# Current_Sensor_v0_6.net
KiCad netlist of a schematic drawn in EAGLE
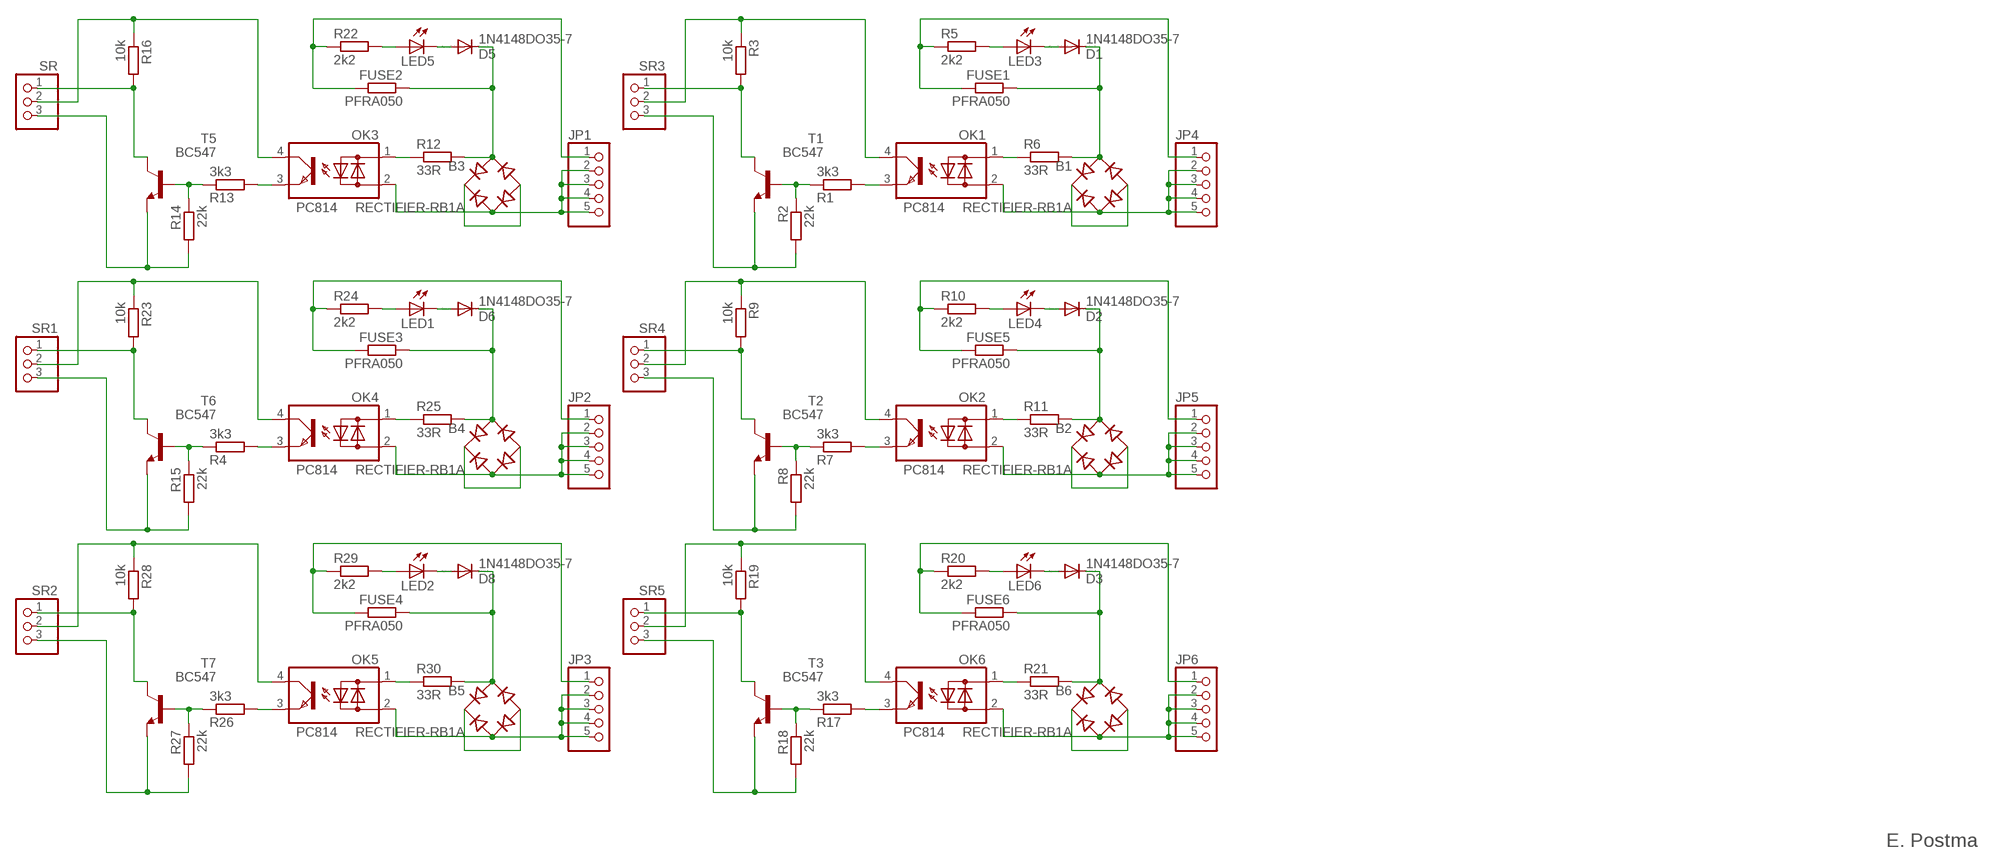
[diagram p0: schematic, sheet 1]

(export (version "E")
  (design (tool "Eeschema 10.0.6"))
  (components
    (comp (ref "B1")
      (value "RECTIFIER-RB1A")
      (footprint "eagle-import:RB1A")
      (libsource (lib "eagle-import") (part "RECTIFIER-RB1A"))
    )
    (comp (ref "B2")
      (value "RECTIFIER-RB1A")
      (footprint "eagle-import:RB1A")
      (libsource (lib "eagle-import") (part "RECTIFIER-RB1A"))
    )
    (comp (ref "B3")
      (value "RECTIFIER-RB1A")
      (footprint "eagle-import:RB1A")
      (libsource (lib "eagle-import") (part "RECTIFIER-RB1A"))
    )
    (comp (ref "B4")
      (value "RECTIFIER-RB1A")
      (footprint "eagle-import:RB1A")
      (libsource (lib "eagle-import") (part "RECTIFIER-RB1A"))
    )
    (comp (ref "B5")
      (value "RECTIFIER-RB1A")
      (footprint "eagle-import:RB1A")
      (libsource (lib "eagle-import") (part "RECTIFIER-RB1A"))
    )
    (comp (ref "B6")
      (value "RECTIFIER-RB1A")
      (footprint "eagle-import:RB1A")
      (libsource (lib "eagle-import") (part "RECTIFIER-RB1A"))
    )
    (comp (ref "D1")
      (value "1N4148DO35-7")
      (footprint "eagle-import:DO35-7")
      (libsource (lib "eagle-import") (part "1N4148DO35-7"))
    )
    (comp (ref "D2")
      (value "1N4148DO35-7")
      (footprint "eagle-import:DO35-7")
      (libsource (lib "eagle-import") (part "1N4148DO35-7"))
    )
    (comp (ref "D3")
      (value "1N4148DO35-7")
      (footprint "eagle-import:DO35-7")
      (libsource (lib "eagle-import") (part "1N4148DO35-7"))
    )
    (comp (ref "D5")
      (value "1N4148DO35-7")
      (footprint "eagle-import:DO35-7")
      (libsource (lib "eagle-import") (part "1N4148DO35-7"))
    )
    (comp (ref "D6")
      (value "1N4148DO35-7")
      (footprint "eagle-import:DO35-7")
      (libsource (lib "eagle-import") (part "1N4148DO35-7"))
    )
    (comp (ref "D8")
      (value "1N4148DO35-7")
      (footprint "eagle-import:DO35-7")
      (libsource (lib "eagle-import") (part "1N4148DO35-7"))
    )
    (comp (ref "FUSE1")
      (value "PFRA050")
      (footprint "eagle-import:0414V")
      (libsource (lib "eagle-import") (part "R-EU_0414/5V"))
    )
    (comp (ref "FUSE2")
      (value "PFRA050")
      (footprint "eagle-import:0414V")
      (libsource (lib "eagle-import") (part "R-EU_0414/5V"))
    )
    (comp (ref "FUSE3")
      (value "PFRA050")
      (footprint "eagle-import:0414V")
      (libsource (lib "eagle-import") (part "R-EU_0414/5V"))
    )
    (comp (ref "FUSE4")
      (value "PFRA050")
      (footprint "eagle-import:0414V")
      (libsource (lib "eagle-import") (part "R-EU_0414/5V"))
    )
    (comp (ref "FUSE5")
      (value "PFRA050")
      (footprint "eagle-import:0414V")
      (libsource (lib "eagle-import") (part "R-EU_0414/5V"))
    )
    (comp (ref "FUSE6")
      (value "PFRA050")
      (footprint "eagle-import:0414V")
      (libsource (lib "eagle-import") (part "R-EU_0414/5V"))
    )
    (comp (ref "JP1")
      (value "PINHD-1X5")
      (footprint "eagle-import:1X05")
      (libsource (lib "eagle-import") (part "PINHD-1X5"))
    )
    (comp (ref "JP2")
      (value "PINHD-1X5")
      (footprint "eagle-import:1X05")
      (libsource (lib "eagle-import") (part "PINHD-1X5"))
    )
    (comp (ref "JP3")
      (value "PINHD-1X5")
      (footprint "eagle-import:1X05")
      (libsource (lib "eagle-import") (part "PINHD-1X5"))
    )
    (comp (ref "JP4")
      (value "PINHD-1X5")
      (footprint "eagle-import:1X05")
      (libsource (lib "eagle-import") (part "PINHD-1X5"))
    )
    (comp (ref "JP5")
      (value "PINHD-1X5")
      (footprint "eagle-import:1X05")
      (libsource (lib "eagle-import") (part "PINHD-1X5"))
    )
    (comp (ref "JP6")
      (value "PINHD-1X5")
      (footprint "eagle-import:1X05")
      (libsource (lib "eagle-import") (part "PINHD-1X5"))
    )
    (comp (ref "LED1")
      (value "LED3MM")
      (footprint "eagle-import:LED3MM")
      (libsource (lib "eagle-import") (part "LED3MM"))
    )
    (comp (ref "LED2")
      (value "LED3MM")
      (footprint "eagle-import:LED3MM")
      (libsource (lib "eagle-import") (part "LED3MM"))
    )
    (comp (ref "LED3")
      (value "LED3MM")
      (footprint "eagle-import:LED3MM")
      (libsource (lib "eagle-import") (part "LED3MM"))
    )
    (comp (ref "LED4")
      (value "LED3MM")
      (footprint "eagle-import:LED3MM")
      (libsource (lib "eagle-import") (part "LED3MM"))
    )
    (comp (ref "LED5")
      (value "LED3MM")
      (footprint "eagle-import:LED3MM")
      (libsource (lib "eagle-import") (part "LED3MM"))
    )
    (comp (ref "LED6")
      (value "LED3MM")
      (footprint "eagle-import:LED3MM")
      (libsource (lib "eagle-import") (part "LED3MM"))
    )
    (comp (ref "OK1")
      (value "PC814")
      (footprint "eagle-import:DIL04")
      (libsource (lib "eagle-import") (part "PC814"))
    )
    (comp (ref "OK2")
      (value "PC814")
      (footprint "eagle-import:DIL04")
      (libsource (lib "eagle-import") (part "PC814"))
    )
    (comp (ref "OK3")
      (value "PC814")
      (footprint "eagle-import:DIL04")
      (libsource (lib "eagle-import") (part "PC814"))
    )
    (comp (ref "OK4")
      (value "PC814")
      (footprint "eagle-import:DIL04")
      (libsource (lib "eagle-import") (part "PC814"))
    )
    (comp (ref "OK5")
      (value "PC814")
      (footprint "eagle-import:DIL04")
      (libsource (lib "eagle-import") (part "PC814"))
    )
    (comp (ref "OK6")
      (value "PC814")
      (footprint "eagle-import:DIL04")
      (libsource (lib "eagle-import") (part "PC814"))
    )
    (comp (ref "R1")
      (value "3k3")
      (footprint "eagle-import:0207_7")
      (libsource (lib "eagle-import") (part "resistor_348_R-EU_0207/7"))
    )
    (comp (ref "R2")
      (value "22k")
      (footprint "eagle-import:0207_7")
      (libsource (lib "eagle-import") (part "resistor_348_R-EU_0207/7"))
    )
    (comp (ref "R3")
      (value "10k")
      (footprint "eagle-import:0207_7")
      (libsource (lib "eagle-import") (part "resistor_348_R-EU_0207/7"))
    )
    (comp (ref "R4")
      (value "3k3")
      (footprint "eagle-import:0207_7")
      (libsource (lib "eagle-import") (part "resistor_348_R-EU_0207/7"))
    )
    (comp (ref "R5")
      (value "2k2")
      (footprint "eagle-import:0207_7")
      (libsource (lib "eagle-import") (part "resistor_348_R-EU_0207/7"))
    )
    (comp (ref "R6")
      (value "33R")
      (footprint "eagle-import:0207_7")
      (libsource (lib "eagle-import") (part "resistor_348_R-EU_0207/7"))
    )
    (comp (ref "R7")
      (value "3k3")
      (footprint "eagle-import:0207_7")
      (libsource (lib "eagle-import") (part "resistor_348_R-EU_0207/7"))
    )
    (comp (ref "R8")
      (value "22k")
      (footprint "eagle-import:0207_7")
      (libsource (lib "eagle-import") (part "resistor_348_R-EU_0207/7"))
    )
    (comp (ref "R9")
      (value "10k")
      (footprint "eagle-import:0207_7")
      (libsource (lib "eagle-import") (part "resistor_348_R-EU_0207/7"))
    )
    (comp (ref "R10")
      (value "2k2")
      (footprint "eagle-import:0207_7")
      (libsource (lib "eagle-import") (part "resistor_348_R-EU_0207/7"))
    )
    (comp (ref "R11")
      (value "33R")
      (footprint "eagle-import:0207_7")
      (libsource (lib "eagle-import") (part "resistor_348_R-EU_0207/7"))
    )
    (comp (ref "R12")
      (value "33R")
      (footprint "eagle-import:0207_7")
      (libsource (lib "eagle-import") (part "resistor_348_R-EU_0207/7"))
    )
    (comp (ref "R13")
      (value "3k3")
      (footprint "eagle-import:0207_7")
      (libsource (lib "eagle-import") (part "resistor_348_R-EU_0207/7"))
    )
    (comp (ref "R14")
      (value "22k")
      (footprint "eagle-import:0207_7")
      (libsource (lib "eagle-import") (part "resistor_348_R-EU_0207/7"))
    )
    (comp (ref "R15")
      (value "22k")
      (footprint "eagle-import:0207_7")
      (libsource (lib "eagle-import") (part "resistor_348_R-EU_0207/7"))
    )
    (comp (ref "R16")
      (value "10k")
      (footprint "eagle-import:0207_7")
      (libsource (lib "eagle-import") (part "resistor_348_R-EU_0207/7"))
    )
    (comp (ref "R17")
      (value "3k3")
      (footprint "eagle-import:0207_7")
      (libsource (lib "eagle-import") (part "resistor_348_R-EU_0207/7"))
    )
    (comp (ref "R18")
      (value "22k")
      (footprint "eagle-import:0207_7")
      (libsource (lib "eagle-import") (part "resistor_348_R-EU_0207/7"))
    )
    (comp (ref "R19")
      (value "10k")
      (footprint "eagle-import:0207_7")
      (libsource (lib "eagle-import") (part "resistor_348_R-EU_0207/7"))
    )
    (comp (ref "R20")
      (value "2k2")
      (footprint "eagle-import:0207_7")
      (libsource (lib "eagle-import") (part "resistor_348_R-EU_0207/7"))
    )
    (comp (ref "R21")
      (value "33R")
      (footprint "eagle-import:0207_7")
      (libsource (lib "eagle-import") (part "resistor_348_R-EU_0207/7"))
    )
    (comp (ref "R22")
      (value "2k2")
      (footprint "eagle-import:0207_7")
      (libsource (lib "eagle-import") (part "resistor_348_R-EU_0207/7"))
    )
    (comp (ref "R23")
      (value "10k")
      (footprint "eagle-import:0207_7")
      (libsource (lib "eagle-import") (part "resistor_348_R-EU_0207/7"))
    )
    (comp (ref "R24")
      (value "2k2")
      (footprint "eagle-import:0207_7")
      (libsource (lib "eagle-import") (part "resistor_348_R-EU_0207/7"))
    )
    (comp (ref "R25")
      (value "33R")
      (footprint "eagle-import:0207_7")
      (libsource (lib "eagle-import") (part "resistor_348_R-EU_0207/7"))
    )
    (comp (ref "R26")
      (value "3k3")
      (footprint "eagle-import:0207_7")
      (libsource (lib "eagle-import") (part "resistor_348_R-EU_0207/7"))
    )
    (comp (ref "R27")
      (value "22k")
      (footprint "eagle-import:0207_7")
      (libsource (lib "eagle-import") (part "resistor_348_R-EU_0207/7"))
    )
    (comp (ref "R28")
      (value "10k")
      (footprint "eagle-import:0207_7")
      (libsource (lib "eagle-import") (part "resistor_348_R-EU_0207/7"))
    )
    (comp (ref "R29")
      (value "2k2")
      (footprint "eagle-import:0207_7")
      (libsource (lib "eagle-import") (part "resistor_348_R-EU_0207/7"))
    )
    (comp (ref "R30")
      (value "33R")
      (footprint "eagle-import:0207_7")
      (libsource (lib "eagle-import") (part "resistor_348_R-EU_0207/7"))
    )
    (comp (ref "SR")
      (value "PINHD-1X3")
      (footprint "eagle-import:1X03")
      (libsource (lib "eagle-import") (part "PINHD-1X3"))
    )
    (comp (ref "SR1")
      (value "PINHD-1X3")
      (footprint "eagle-import:1X03")
      (libsource (lib "eagle-import") (part "PINHD-1X3"))
    )
    (comp (ref "SR2")
      (value "PINHD-1X3")
      (footprint "eagle-import:1X03")
      (libsource (lib "eagle-import") (part "PINHD-1X3"))
    )
    (comp (ref "SR3")
      (value "PINHD-1X3")
      (footprint "eagle-import:1X03")
      (libsource (lib "eagle-import") (part "PINHD-1X3"))
    )
    (comp (ref "SR4")
      (value "PINHD-1X3")
      (footprint "eagle-import:1X03")
      (libsource (lib "eagle-import") (part "PINHD-1X3"))
    )
    (comp (ref "SR5")
      (value "PINHD-1X3")
      (footprint "eagle-import:1X03")
      (libsource (lib "eagle-import") (part "PINHD-1X3"))
    )
    (comp (ref "T1")
      (value "BC547")
      (footprint "eagle-import:TO92")
      (libsource (lib "eagle-import") (part "BC547"))
    )
    (comp (ref "T2")
      (value "BC547")
      (footprint "eagle-import:TO92")
      (libsource (lib "eagle-import") (part "BC547"))
    )
    (comp (ref "T3")
      (value "BC547")
      (footprint "eagle-import:TO92")
      (libsource (lib "eagle-import") (part "BC547"))
    )
    (comp (ref "T5")
      (value "BC547")
      (footprint "eagle-import:TO92")
      (libsource (lib "eagle-import") (part "BC547"))
    )
    (comp (ref "T6")
      (value "BC547")
      (footprint "eagle-import:TO92")
      (libsource (lib "eagle-import") (part "BC547"))
    )
    (comp (ref "T7")
      (value "BC547")
      (footprint "eagle-import:TO92")
      (libsource (lib "eagle-import") (part "BC547"))
    )
  )
  (nets
    (net (code "1") (name "Net-(B1-Pad+)") (class "Default")
      (node (ref "B1") (pin "+") (pinfunction "+_+") (pintype "passive"))
      (node (ref "B1") (pin "-") (pinfunction "-_-") (pintype "passive"))
    )
    (net (code "2") (name "Net-(B1-PadAC1)") (class "Default")
      (node (ref "B1") (pin "AC1") (pinfunction "AC1_AC1") (pintype "passive"))
      (node (ref "D1") (pin "C") (pinfunction "C_C") (pintype "passive"))
      (node (ref "FUSE1") (pin "1") (pinfunction "1_1") (pintype "passive"))
      (node (ref "R6") (pin "2") (pinfunction "2_2") (pintype "passive"))
    )
    (net (code "3") (name "Net-(B2-Pad+)") (class "Default")
      (node (ref "B2") (pin "+") (pinfunction "+_+") (pintype "passive"))
      (node (ref "B2") (pin "-") (pinfunction "-_-") (pintype "passive"))
    )
    (net (code "4") (name "Net-(B2-PadAC1)") (class "Default")
      (node (ref "B2") (pin "AC1") (pinfunction "AC1_AC1") (pintype "passive"))
      (node (ref "D2") (pin "C") (pinfunction "C_C") (pintype "passive"))
      (node (ref "FUSE5") (pin "1") (pinfunction "1_1") (pintype "passive"))
      (node (ref "R11") (pin "2") (pinfunction "2_2") (pintype "passive"))
    )
    (net (code "5") (name "Net-(B3-Pad+)") (class "Default")
      (node (ref "B3") (pin "+") (pinfunction "+_+") (pintype "passive"))
      (node (ref "B3") (pin "-") (pinfunction "-_-") (pintype "passive"))
    )
    (net (code "6") (name "Net-(B3-PadAC1)") (class "Default")
      (node (ref "B3") (pin "AC1") (pinfunction "AC1_AC1") (pintype "passive"))
      (node (ref "D5") (pin "C") (pinfunction "C_C") (pintype "passive"))
      (node (ref "FUSE2") (pin "1") (pinfunction "1_1") (pintype "passive"))
      (node (ref "R12") (pin "2") (pinfunction "2_2") (pintype "passive"))
    )
    (net (code "7") (name "Net-(B4-Pad+)") (class "Default")
      (node (ref "B4") (pin "+") (pinfunction "+_+") (pintype "passive"))
      (node (ref "B4") (pin "-") (pinfunction "-_-") (pintype "passive"))
    )
    (net (code "8") (name "Net-(B4-PadAC1)") (class "Default")
      (node (ref "B4") (pin "AC1") (pinfunction "AC1_AC1") (pintype "passive"))
      (node (ref "D6") (pin "C") (pinfunction "C_C") (pintype "passive"))
      (node (ref "FUSE3") (pin "1") (pinfunction "1_1") (pintype "passive"))
      (node (ref "R25") (pin "2") (pinfunction "2_2") (pintype "passive"))
    )
    (net (code "9") (name "Net-(B5-Pad+)") (class "Default")
      (node (ref "B5") (pin "+") (pinfunction "+_+") (pintype "passive"))
      (node (ref "B5") (pin "-") (pinfunction "-_-") (pintype "passive"))
    )
    (net (code "10") (name "Net-(B5-PadAC1)") (class "Default")
      (node (ref "B5") (pin "AC1") (pinfunction "AC1_AC1") (pintype "passive"))
      (node (ref "D8") (pin "C") (pinfunction "C_C") (pintype "passive"))
      (node (ref "FUSE4") (pin "1") (pinfunction "1_1") (pintype "passive"))
      (node (ref "R30") (pin "2") (pinfunction "2_2") (pintype "passive"))
    )
    (net (code "11") (name "Net-(B6-Pad+)") (class "Default")
      (node (ref "B6") (pin "+") (pinfunction "+_+") (pintype "passive"))
      (node (ref "B6") (pin "-") (pinfunction "-_-") (pintype "passive"))
    )
    (net (code "12") (name "Net-(B6-PadAC1)") (class "Default")
      (node (ref "B6") (pin "AC1") (pinfunction "AC1_AC1") (pintype "passive"))
      (node (ref "D3") (pin "C") (pinfunction "C_C") (pintype "passive"))
      (node (ref "FUSE6") (pin "1") (pinfunction "1_1") (pintype "passive"))
      (node (ref "R21") (pin "2") (pinfunction "2_2") (pintype "passive"))
    )
    (net (code "13") (name "Net-(FUSE1-Pad2)") (class "Default")
      (node (ref "FUSE1") (pin "2") (pinfunction "2_2") (pintype "passive"))
      (node (ref "JP4") (pin "1") (pinfunction "1_1") (pintype "passive"))
      (node (ref "R5") (pin "1") (pinfunction "1_1") (pintype "passive"))
    )
    (net (code "14") (name "Net-(FUSE2-Pad2)") (class "Default")
      (node (ref "FUSE2") (pin "2") (pinfunction "2_2") (pintype "passive"))
      (node (ref "JP1") (pin "1") (pinfunction "1_1") (pintype "passive"))
      (node (ref "R22") (pin "1") (pinfunction "1_1") (pintype "passive"))
    )
    (net (code "15") (name "Net-(FUSE3-Pad2)") (class "Default")
      (node (ref "FUSE3") (pin "2") (pinfunction "2_2") (pintype "passive"))
      (node (ref "JP2") (pin "1") (pinfunction "1_1") (pintype "passive"))
      (node (ref "R24") (pin "1") (pinfunction "1_1") (pintype "passive"))
    )
    (net (code "16") (name "Net-(FUSE4-Pad2)") (class "Default")
      (node (ref "FUSE4") (pin "2") (pinfunction "2_2") (pintype "passive"))
      (node (ref "JP3") (pin "1") (pinfunction "1_1") (pintype "passive"))
      (node (ref "R29") (pin "1") (pinfunction "1_1") (pintype "passive"))
    )
    (net (code "17") (name "Net-(FUSE5-Pad2)") (class "Default")
      (node (ref "FUSE5") (pin "2") (pinfunction "2_2") (pintype "passive"))
      (node (ref "JP5") (pin "1") (pinfunction "1_1") (pintype "passive"))
      (node (ref "R10") (pin "1") (pinfunction "1_1") (pintype "passive"))
    )
    (net (code "18") (name "Net-(FUSE6-Pad2)") (class "Default")
      (node (ref "FUSE6") (pin "2") (pinfunction "2_2") (pintype "passive"))
      (node (ref "JP6") (pin "1") (pinfunction "1_1") (pintype "passive"))
      (node (ref "R20") (pin "1") (pinfunction "1_1") (pintype "passive"))
    )
    (net (code "19") (name "Net-(LED1-C)") (class "Default")
      (node (ref "D6") (pin "A") (pinfunction "A_A") (pintype "passive"))
      (node (ref "LED1") (pin "K") (pinfunction "C_K") (pintype "passive"))
    )
    (net (code "20") (name "Net-(LED1-PadA)") (class "Default")
      (node (ref "LED1") (pin "A") (pinfunction "A_A") (pintype "passive"))
      (node (ref "R24") (pin "2") (pinfunction "2_2") (pintype "passive"))
    )
    (net (code "21") (name "Net-(LED2-C)") (class "Default")
      (node (ref "D8") (pin "A") (pinfunction "A_A") (pintype "passive"))
      (node (ref "LED2") (pin "K") (pinfunction "C_K") (pintype "passive"))
    )
    (net (code "22") (name "Net-(LED2-PadA)") (class "Default")
      (node (ref "LED2") (pin "A") (pinfunction "A_A") (pintype "passive"))
      (node (ref "R29") (pin "2") (pinfunction "2_2") (pintype "passive"))
    )
    (net (code "23") (name "Net-(LED3-C)") (class "Default")
      (node (ref "D1") (pin "A") (pinfunction "A_A") (pintype "passive"))
      (node (ref "LED3") (pin "K") (pinfunction "C_K") (pintype "passive"))
    )
    (net (code "24") (name "Net-(LED3-PadA)") (class "Default")
      (node (ref "LED3") (pin "A") (pinfunction "A_A") (pintype "passive"))
      (node (ref "R5") (pin "2") (pinfunction "2_2") (pintype "passive"))
    )
    (net (code "25") (name "Net-(LED4-C)") (class "Default")
      (node (ref "D2") (pin "A") (pinfunction "A_A") (pintype "passive"))
      (node (ref "LED4") (pin "K") (pinfunction "C_K") (pintype "passive"))
    )
    (net (code "26") (name "Net-(LED4-PadA)") (class "Default")
      (node (ref "LED4") (pin "A") (pinfunction "A_A") (pintype "passive"))
      (node (ref "R10") (pin "2") (pinfunction "2_2") (pintype "passive"))
    )
    (net (code "27") (name "Net-(LED5-C)") (class "Default")
      (node (ref "D5") (pin "A") (pinfunction "A_A") (pintype "passive"))
      (node (ref "LED5") (pin "K") (pinfunction "C_K") (pintype "passive"))
    )
    (net (code "28") (name "Net-(LED5-PadA)") (class "Default")
      (node (ref "LED5") (pin "A") (pinfunction "A_A") (pintype "passive"))
      (node (ref "R22") (pin "2") (pinfunction "2_2") (pintype "passive"))
    )
    (net (code "29") (name "Net-(LED6-C)") (class "Default")
      (node (ref "D3") (pin "A") (pinfunction "A_A") (pintype "passive"))
      (node (ref "LED6") (pin "K") (pinfunction "C_K") (pintype "passive"))
    )
    (net (code "30") (name "Net-(LED6-PadA)") (class "Default")
      (node (ref "LED6") (pin "A") (pinfunction "A_A") (pintype "passive"))
      (node (ref "R20") (pin "2") (pinfunction "2_2") (pintype "passive"))
    )
    (net (code "31") (name "Net-(OK1-AC1)") (class "Default")
      (node (ref "OK1") (pin "1") (pinfunction "AC1_1") (pintype "passive"))
      (node (ref "R6") (pin "1") (pinfunction "1_1") (pintype "passive"))
    )
    (net (code "32") (name "Net-(OK1-AC2)") (class "Default")
      (node (ref "B1") (pin "AC2") (pinfunction "AC2_AC2") (pintype "passive"))
      (node (ref "JP4") (pin "2") (pinfunction "2_2") (pintype "passive"))
      (node (ref "JP4") (pin "3") (pinfunction "3_3") (pintype "passive"))
      (node (ref "JP4") (pin "4") (pinfunction "4_4") (pintype "passive"))
      (node (ref "JP4") (pin "5") (pinfunction "5_5") (pintype "passive"))
      (node (ref "OK1") (pin "2") (pinfunction "AC2_2") (pintype "passive"))
    )
    (net (code "33") (name "Net-(OK1-C)") (class "Default")
      (node (ref "OK1") (pin "4") (pinfunction "C_4") (pintype "passive"))
      (node (ref "R3") (pin "1") (pinfunction "1_1") (pintype "passive"))
      (node (ref "SR3") (pin "2") (pinfunction "2_2") (pintype "passive"))
    )
    (net (code "34") (name "Net-(OK1-E)") (class "Default")
      (node (ref "OK1") (pin "3") (pinfunction "E_3") (pintype "passive"))
      (node (ref "R1") (pin "2") (pinfunction "2_2") (pintype "passive"))
    )
    (net (code "35") (name "Net-(OK2-AC1)") (class "Default")
      (node (ref "OK2") (pin "1") (pinfunction "AC1_1") (pintype "passive"))
      (node (ref "R11") (pin "1") (pinfunction "1_1") (pintype "passive"))
    )
    (net (code "36") (name "Net-(OK2-AC2)") (class "Default")
      (node (ref "B2") (pin "AC2") (pinfunction "AC2_AC2") (pintype "passive"))
      (node (ref "JP5") (pin "2") (pinfunction "2_2") (pintype "passive"))
      (node (ref "JP5") (pin "3") (pinfunction "3_3") (pintype "passive"))
      (node (ref "JP5") (pin "4") (pinfunction "4_4") (pintype "passive"))
      (node (ref "JP5") (pin "5") (pinfunction "5_5") (pintype "passive"))
      (node (ref "OK2") (pin "2") (pinfunction "AC2_2") (pintype "passive"))
    )
    (net (code "37") (name "Net-(OK2-C)") (class "Default")
      (node (ref "OK2") (pin "4") (pinfunction "C_4") (pintype "passive"))
      (node (ref "R9") (pin "1") (pinfunction "1_1") (pintype "passive"))
      (node (ref "SR4") (pin "2") (pinfunction "2_2") (pintype "passive"))
    )
    (net (code "38") (name "Net-(OK2-E)") (class "Default")
      (node (ref "OK2") (pin "3") (pinfunction "E_3") (pintype "passive"))
      (node (ref "R7") (pin "2") (pinfunction "2_2") (pintype "passive"))
    )
    (net (code "39") (name "Net-(OK3-AC1)") (class "Default")
      (node (ref "OK3") (pin "1") (pinfunction "AC1_1") (pintype "passive"))
      (node (ref "R12") (pin "1") (pinfunction "1_1") (pintype "passive"))
    )
    (net (code "40") (name "Net-(OK3-AC2)") (class "Default")
      (node (ref "B3") (pin "AC2") (pinfunction "AC2_AC2") (pintype "passive"))
      (node (ref "JP1") (pin "2") (pinfunction "2_2") (pintype "passive"))
      (node (ref "JP1") (pin "3") (pinfunction "3_3") (pintype "passive"))
      (node (ref "JP1") (pin "4") (pinfunction "4_4") (pintype "passive"))
      (node (ref "JP1") (pin "5") (pinfunction "5_5") (pintype "passive"))
      (node (ref "OK3") (pin "2") (pinfunction "AC2_2") (pintype "passive"))
    )
    (net (code "41") (name "Net-(OK3-C)") (class "Default")
      (node (ref "OK3") (pin "4") (pinfunction "C_4") (pintype "passive"))
      (node (ref "R16") (pin "1") (pinfunction "1_1") (pintype "passive"))
      (node (ref "SR") (pin "2") (pinfunction "2_2") (pintype "passive"))
    )
    (net (code "42") (name "Net-(OK3-E)") (class "Default")
      (node (ref "OK3") (pin "3") (pinfunction "E_3") (pintype "passive"))
      (node (ref "R13") (pin "2") (pinfunction "2_2") (pintype "passive"))
    )
    (net (code "43") (name "Net-(OK4-AC1)") (class "Default")
      (node (ref "OK4") (pin "1") (pinfunction "AC1_1") (pintype "passive"))
      (node (ref "R25") (pin "1") (pinfunction "1_1") (pintype "passive"))
    )
    (net (code "44") (name "Net-(OK4-AC2)") (class "Default")
      (node (ref "B4") (pin "AC2") (pinfunction "AC2_AC2") (pintype "passive"))
      (node (ref "JP2") (pin "2") (pinfunction "2_2") (pintype "passive"))
      (node (ref "JP2") (pin "3") (pinfunction "3_3") (pintype "passive"))
      (node (ref "JP2") (pin "4") (pinfunction "4_4") (pintype "passive"))
      (node (ref "JP2") (pin "5") (pinfunction "5_5") (pintype "passive"))
      (node (ref "OK4") (pin "2") (pinfunction "AC2_2") (pintype "passive"))
    )
    (net (code "45") (name "Net-(OK4-C)") (class "Default")
      (node (ref "OK4") (pin "4") (pinfunction "C_4") (pintype "passive"))
      (node (ref "R23") (pin "1") (pinfunction "1_1") (pintype "passive"))
      (node (ref "SR1") (pin "2") (pinfunction "2_2") (pintype "passive"))
    )
    (net (code "46") (name "Net-(OK4-E)") (class "Default")
      (node (ref "OK4") (pin "3") (pinfunction "E_3") (pintype "passive"))
      (node (ref "R4") (pin "2") (pinfunction "2_2") (pintype "passive"))
    )
    (net (code "47") (name "Net-(OK5-AC1)") (class "Default")
      (node (ref "OK5") (pin "1") (pinfunction "AC1_1") (pintype "passive"))
      (node (ref "R30") (pin "1") (pinfunction "1_1") (pintype "passive"))
    )
    (net (code "48") (name "Net-(OK5-AC2)") (class "Default")
      (node (ref "B5") (pin "AC2") (pinfunction "AC2_AC2") (pintype "passive"))
      (node (ref "JP3") (pin "2") (pinfunction "2_2") (pintype "passive"))
      (node (ref "JP3") (pin "3") (pinfunction "3_3") (pintype "passive"))
      (node (ref "JP3") (pin "4") (pinfunction "4_4") (pintype "passive"))
      (node (ref "JP3") (pin "5") (pinfunction "5_5") (pintype "passive"))
      (node (ref "OK5") (pin "2") (pinfunction "AC2_2") (pintype "passive"))
    )
    (net (code "49") (name "Net-(OK5-C)") (class "Default")
      (node (ref "OK5") (pin "4") (pinfunction "C_4") (pintype "passive"))
      (node (ref "R28") (pin "1") (pinfunction "1_1") (pintype "passive"))
      (node (ref "SR2") (pin "2") (pinfunction "2_2") (pintype "passive"))
    )
    (net (code "50") (name "Net-(OK5-E)") (class "Default")
      (node (ref "OK5") (pin "3") (pinfunction "E_3") (pintype "passive"))
      (node (ref "R26") (pin "2") (pinfunction "2_2") (pintype "passive"))
    )
    (net (code "51") (name "Net-(OK6-AC1)") (class "Default")
      (node (ref "OK6") (pin "1") (pinfunction "AC1_1") (pintype "passive"))
      (node (ref "R21") (pin "1") (pinfunction "1_1") (pintype "passive"))
    )
    (net (code "52") (name "Net-(OK6-AC2)") (class "Default")
      (node (ref "B6") (pin "AC2") (pinfunction "AC2_AC2") (pintype "passive"))
      (node (ref "JP6") (pin "2") (pinfunction "2_2") (pintype "passive"))
      (node (ref "JP6") (pin "3") (pinfunction "3_3") (pintype "passive"))
      (node (ref "JP6") (pin "4") (pinfunction "4_4") (pintype "passive"))
      (node (ref "JP6") (pin "5") (pinfunction "5_5") (pintype "passive"))
      (node (ref "OK6") (pin "2") (pinfunction "AC2_2") (pintype "passive"))
    )
    (net (code "53") (name "Net-(OK6-C)") (class "Default")
      (node (ref "OK6") (pin "4") (pinfunction "C_4") (pintype "passive"))
      (node (ref "R19") (pin "1") (pinfunction "1_1") (pintype "passive"))
      (node (ref "SR5") (pin "2") (pinfunction "2_2") (pintype "passive"))
    )
    (net (code "54") (name "Net-(OK6-E)") (class "Default")
      (node (ref "OK6") (pin "3") (pinfunction "E_3") (pintype "passive"))
      (node (ref "R17") (pin "2") (pinfunction "2_2") (pintype "passive"))
    )
    (net (code "55") (name "Net-(T1-B)") (class "Default")
      (node (ref "R1") (pin "1") (pinfunction "1_1") (pintype "passive"))
      (node (ref "R2") (pin "1") (pinfunction "1_1") (pintype "passive"))
      (node (ref "T1") (pin "2") (pinfunction "B_2") (pintype "passive"))
    )
    (net (code "56") (name "Net-(T1-C)") (class "Default")
      (node (ref "R3") (pin "2") (pinfunction "2_2") (pintype "passive"))
      (node (ref "SR3") (pin "1") (pinfunction "1_1") (pintype "passive"))
      (node (ref "T1") (pin "3") (pinfunction "C_3") (pintype "passive"))
    )
    (net (code "57") (name "Net-(T1-E)") (class "Default")
      (node (ref "R2") (pin "2") (pinfunction "2_2") (pintype "passive"))
      (node (ref "SR3") (pin "3") (pinfunction "3_3") (pintype "passive"))
      (node (ref "T1") (pin "1") (pinfunction "E_1") (pintype "passive"))
    )
    (net (code "58") (name "Net-(T2-B)") (class "Default")
      (node (ref "R7") (pin "1") (pinfunction "1_1") (pintype "passive"))
      (node (ref "R8") (pin "1") (pinfunction "1_1") (pintype "passive"))
      (node (ref "T2") (pin "2") (pinfunction "B_2") (pintype "passive"))
    )
    (net (code "59") (name "Net-(T2-C)") (class "Default")
      (node (ref "R9") (pin "2") (pinfunction "2_2") (pintype "passive"))
      (node (ref "SR4") (pin "1") (pinfunction "1_1") (pintype "passive"))
      (node (ref "T2") (pin "3") (pinfunction "C_3") (pintype "passive"))
    )
    (net (code "60") (name "Net-(T2-E)") (class "Default")
      (node (ref "R8") (pin "2") (pinfunction "2_2") (pintype "passive"))
      (node (ref "SR4") (pin "3") (pinfunction "3_3") (pintype "passive"))
      (node (ref "T2") (pin "1") (pinfunction "E_1") (pintype "passive"))
    )
    (net (code "61") (name "Net-(T3-B)") (class "Default")
      (node (ref "R17") (pin "1") (pinfunction "1_1") (pintype "passive"))
      (node (ref "R18") (pin "1") (pinfunction "1_1") (pintype "passive"))
      (node (ref "T3") (pin "2") (pinfunction "B_2") (pintype "passive"))
    )
    (net (code "62") (name "Net-(T3-C)") (class "Default")
      (node (ref "R19") (pin "2") (pinfunction "2_2") (pintype "passive"))
      (node (ref "SR5") (pin "1") (pinfunction "1_1") (pintype "passive"))
      (node (ref "T3") (pin "3") (pinfunction "C_3") (pintype "passive"))
    )
    (net (code "63") (name "Net-(T3-E)") (class "Default")
      (node (ref "R18") (pin "2") (pinfunction "2_2") (pintype "passive"))
      (node (ref "SR5") (pin "3") (pinfunction "3_3") (pintype "passive"))
      (node (ref "T3") (pin "1") (pinfunction "E_1") (pintype "passive"))
    )
    (net (code "64") (name "Net-(T5-B)") (class "Default")
      (node (ref "R13") (pin "1") (pinfunction "1_1") (pintype "passive"))
      (node (ref "R14") (pin "1") (pinfunction "1_1") (pintype "passive"))
      (node (ref "T5") (pin "2") (pinfunction "B_2") (pintype "passive"))
    )
    (net (code "65") (name "Net-(T5-C)") (class "Default")
      (node (ref "R16") (pin "2") (pinfunction "2_2") (pintype "passive"))
      (node (ref "SR") (pin "1") (pinfunction "1_1") (pintype "passive"))
      (node (ref "T5") (pin "3") (pinfunction "C_3") (pintype "passive"))
    )
    (net (code "66") (name "Net-(T5-E)") (class "Default")
      (node (ref "R14") (pin "2") (pinfunction "2_2") (pintype "passive"))
      (node (ref "SR") (pin "3") (pinfunction "3_3") (pintype "passive"))
      (node (ref "T5") (pin "1") (pinfunction "E_1") (pintype "passive"))
    )
    (net (code "67") (name "Net-(T6-B)") (class "Default")
      (node (ref "R15") (pin "1") (pinfunction "1_1") (pintype "passive"))
      (node (ref "R4") (pin "1") (pinfunction "1_1") (pintype "passive"))
      (node (ref "T6") (pin "2") (pinfunction "B_2") (pintype "passive"))
    )
    (net (code "68") (name "Net-(T6-C)") (class "Default")
      (node (ref "R23") (pin "2") (pinfunction "2_2") (pintype "passive"))
      (node (ref "SR1") (pin "1") (pinfunction "1_1") (pintype "passive"))
      (node (ref "T6") (pin "3") (pinfunction "C_3") (pintype "passive"))
    )
    (net (code "69") (name "Net-(T6-E)") (class "Default")
      (node (ref "R15") (pin "2") (pinfunction "2_2") (pintype "passive"))
      (node (ref "SR1") (pin "3") (pinfunction "3_3") (pintype "passive"))
      (node (ref "T6") (pin "1") (pinfunction "E_1") (pintype "passive"))
    )
    (net (code "70") (name "Net-(T7-B)") (class "Default")
      (node (ref "R26") (pin "1") (pinfunction "1_1") (pintype "passive"))
      (node (ref "R27") (pin "1") (pinfunction "1_1") (pintype "passive"))
      (node (ref "T7") (pin "2") (pinfunction "B_2") (pintype "passive"))
    )
    (net (code "71") (name "Net-(T7-C)") (class "Default")
      (node (ref "R28") (pin "2") (pinfunction "2_2") (pintype "passive"))
      (node (ref "SR2") (pin "1") (pinfunction "1_1") (pintype "passive"))
      (node (ref "T7") (pin "3") (pinfunction "C_3") (pintype "passive"))
    )
    (net (code "72") (name "Net-(T7-E)") (class "Default")
      (node (ref "R27") (pin "2") (pinfunction "2_2") (pintype "passive"))
      (node (ref "SR2") (pin "3") (pinfunction "3_3") (pintype "passive"))
      (node (ref "T7") (pin "1") (pinfunction "E_1") (pintype "passive"))
    )
  )
)
